# SensorBoard.net
KiCad netlist of a schematic drawn in EAGLE
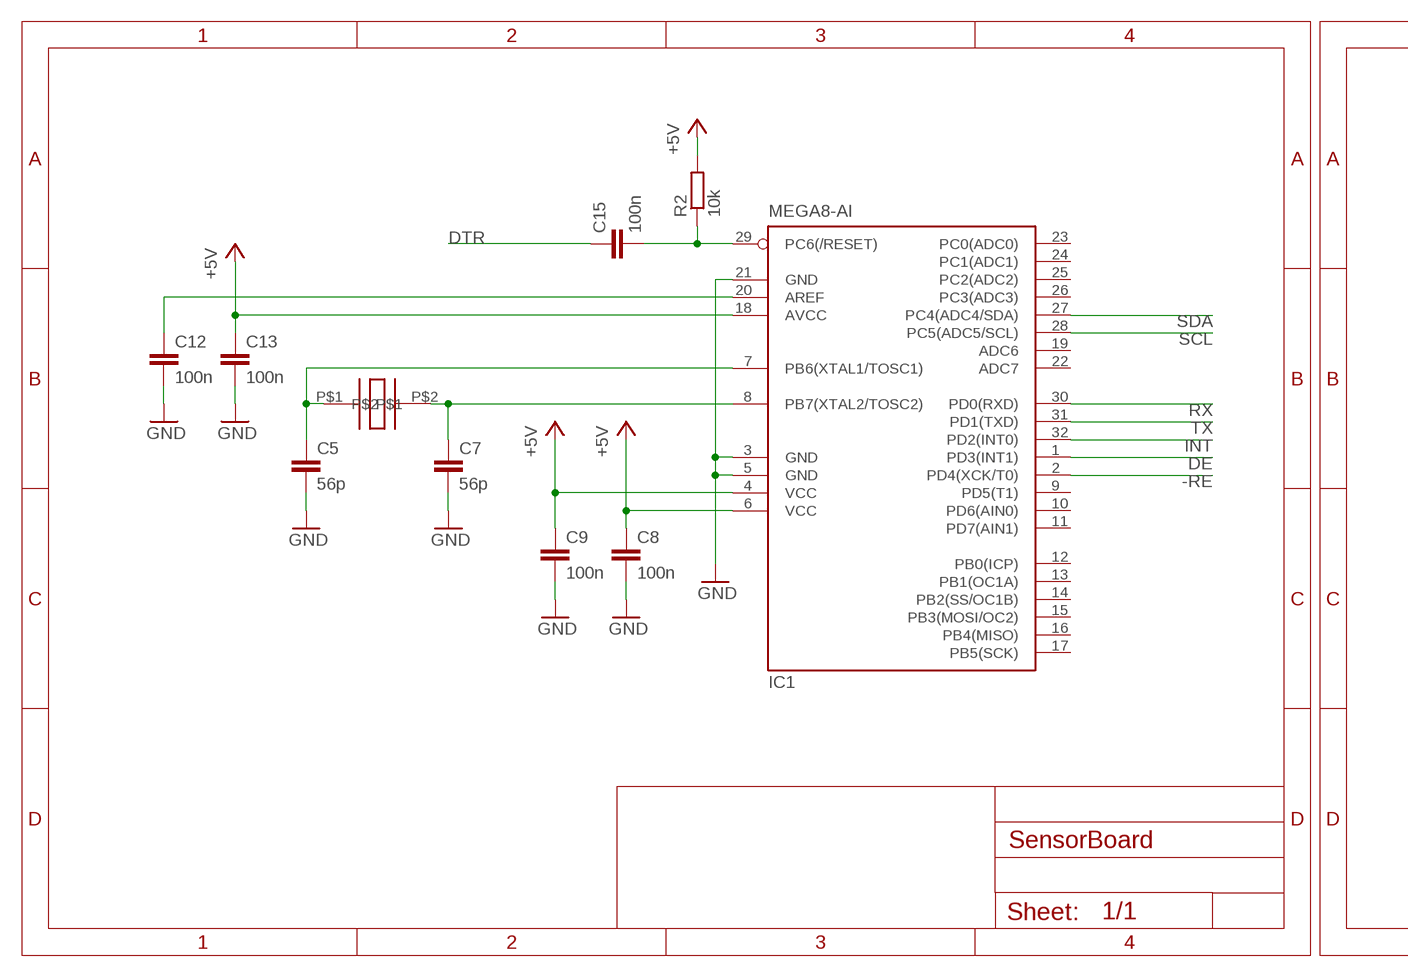
[diagram p0: schematic, sheet 1, part 1 of 2]
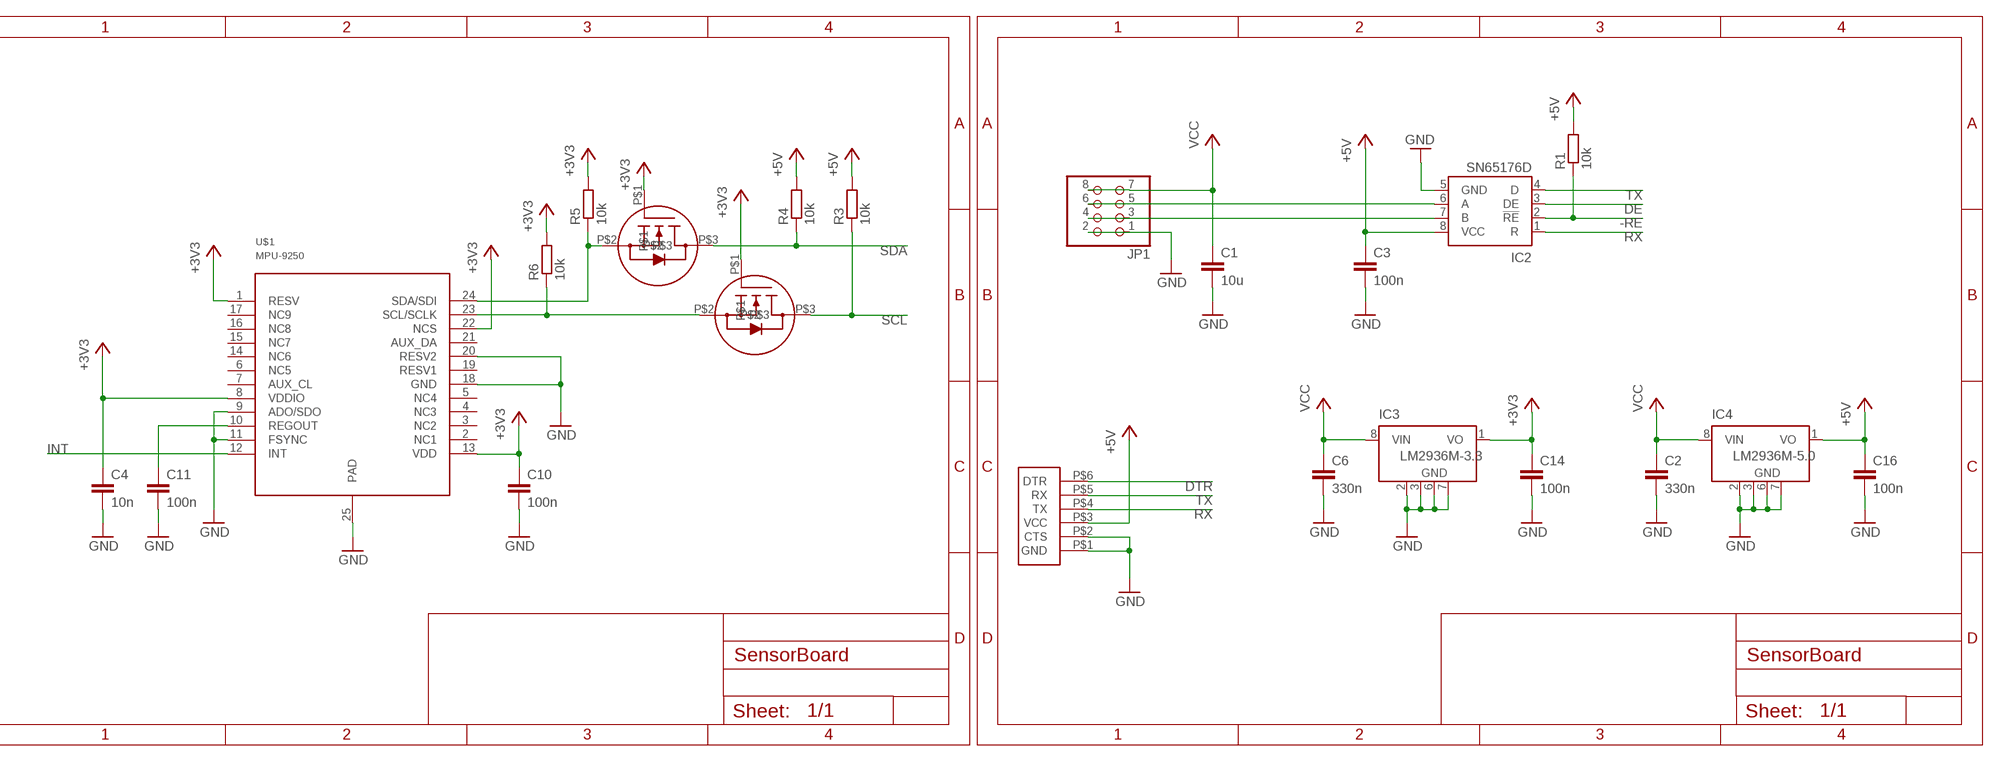
[diagram p1: schematic, sheet 1, part 2 of 2]

(export (version "E")
  (design (tool "Eeschema 10.0.6"))
  (components
    (comp (ref "C1")
      (value "10u")
      (footprint "eagle-import:C0805")
      (libsource (lib "eagle-import") (part "C-EUC0805"))
    )
    (comp (ref "C2")
      (value "330n")
      (footprint "eagle-import:C0603")
      (libsource (lib "eagle-import") (part "C-EUC0603"))
    )
    (comp (ref "C3")
      (value "100n")
      (footprint "eagle-import:C0603")
      (libsource (lib "eagle-import") (part "C-EUC0603"))
    )
    (comp (ref "C4")
      (value "10n")
      (footprint "eagle-import:C0603")
      (libsource (lib "eagle-import") (part "C-EUC0603"))
    )
    (comp (ref "C5")
      (value "56p")
      (footprint "eagle-import:C0603")
      (libsource (lib "eagle-import") (part "C-EUC0603"))
    )
    (comp (ref "C6")
      (value "330n")
      (footprint "eagle-import:C0603")
      (libsource (lib "eagle-import") (part "C-EUC0603"))
    )
    (comp (ref "C7")
      (value "56p")
      (footprint "eagle-import:C0603")
      (libsource (lib "eagle-import") (part "C-EUC0603"))
    )
    (comp (ref "C8")
      (value "100n")
      (footprint "eagle-import:C0603")
      (libsource (lib "eagle-import") (part "C-EUC0603"))
    )
    (comp (ref "C9")
      (value "100n")
      (footprint "eagle-import:C0603")
      (libsource (lib "eagle-import") (part "C-EUC0603"))
    )
    (comp (ref "C10")
      (value "100n")
      (footprint "eagle-import:C0603")
      (libsource (lib "eagle-import") (part "C-EUC0603"))
    )
    (comp (ref "C11")
      (value "100n")
      (footprint "eagle-import:C0603")
      (libsource (lib "eagle-import") (part "C-EUC0603"))
    )
    (comp (ref "C12")
      (value "100n")
      (footprint "eagle-import:C0603")
      (libsource (lib "eagle-import") (part "C-EUC0603"))
    )
    (comp (ref "C13")
      (value "100n")
      (footprint "eagle-import:C0603")
      (libsource (lib "eagle-import") (part "C-EUC0603"))
    )
    (comp (ref "C14")
      (value "100n")
      (footprint "eagle-import:C0603")
      (libsource (lib "eagle-import") (part "C-EUC0603"))
    )
    (comp (ref "C15")
      (value "100n")
      (footprint "eagle-import:C0603")
      (libsource (lib "eagle-import") (part "C-EUC0603"))
    )
    (comp (ref "C16")
      (value "100n")
      (footprint "eagle-import:C0603")
      (libsource (lib "eagle-import") (part "C-EUC0603"))
    )
    (comp (ref "IC1")
      (value "MEGA8-AI")
      (footprint "eagle-import:TQFP32-08")
      (fields (field (name "MPN") "ATMEGA8-16AU"))
      (libsource (lib "eagle-import") (part "MEGA8-AI"))
    )
    (comp (ref "IC2")
      (value "SN65176D")
      (footprint "eagle-import:SO-08")
      (fields (field (name "MF") "TEXAS INSTRUMENTS") (field (name "MPN") "SN65176BD"))
      (libsource (lib "eagle-import") (part "SN65176D"))
    )
    (comp (ref "IC3")
      (value "LM2936M-3.3")
      (footprint "eagle-import:SO08")
      (fields (field (name "MF") "NATIONAL SEMICONDUCTOR") (field (name "MPN") "LM2936M-3.3/NOPB"))
      (libsource (lib "eagle-import") (part "LM2936M?-3.3"))
    )
    (comp (ref "IC4")
      (value "LM2936M-5.0")
      (footprint "eagle-import:SO08")
      (fields (field (name "MF") "NATIONAL SEMICONDUCTOR") (field (name "MPN") "LM2936M-5.0/NOPB"))
      (libsource (lib "eagle-import") (part "LM2936M?-5.0"))
    )
    (comp (ref "JP1")
      (value "PINHD-2X4/90")
      (footprint "eagle-import:2X04_90")
      (libsource (lib "eagle-import") (part "PINHD-2X4/90"))
    )
    (comp (ref "R1")
      (value "10k")
      (footprint "eagle-import:R0603")
      (libsource (lib "eagle-import") (part "R-EU_R0603"))
    )
    (comp (ref "R2")
      (value "10k")
      (footprint "eagle-import:R0603")
      (libsource (lib "eagle-import") (part "R-EU_R0603"))
    )
    (comp (ref "R3")
      (value "10k")
      (footprint "eagle-import:R0603")
      (libsource (lib "eagle-import") (part "R-EU_R0603"))
    )
    (comp (ref "R4")
      (value "10k")
      (footprint "eagle-import:R0603")
      (libsource (lib "eagle-import") (part "R-EU_R0603"))
    )
    (comp (ref "R5")
      (value "10k")
      (footprint "eagle-import:R0603")
      (libsource (lib "eagle-import") (part "R-EU_R0603"))
    )
    (comp (ref "R6")
      (value "10k")
      (footprint "eagle-import:R0603")
      (libsource (lib "eagle-import") (part "R-EU_R0603"))
    )
    (comp (ref "U$1")
      (value "MPU-9250")
      (footprint "eagle-import:LEAD-QFN24")
      (libsource (lib "eagle-import") (part "MPU-9250"))
    )
    (comp (ref "U$2")
      (value "2N7002E")
      (footprint "eagle-import:SOT-23-3")
      (libsource (lib "eagle-import") (part "2N7002E"))
    )
    (comp (ref "U$3")
      (value "2N7002E")
      (footprint "eagle-import:SOT-23-3")
      (libsource (lib "eagle-import") (part "2N7002E"))
    )
    (comp (ref "U$4")
      (value "LFXTAL003240BULK")
      (footprint "eagle-import:LFXTAL003240BULK")
      (libsource (lib "eagle-import") (part "LFXTAL003240BULK"))
    )
    (comp (ref "U$5")
      (value "FTDI-PINHEADER")
      (footprint "eagle-import:FTDI-PINHEADER")
      (libsource (lib "eagle-import") (part "FTDI-PINHEADER"))
    )
  )
  (nets
    (net (code "1") (name "+3V3") (class "Default")
      (node (ref "C10") (pin "1") (pinfunction "1_1") (pintype "passive"))
      (node (ref "C14") (pin "1") (pinfunction "1_1") (pintype "passive"))
      (node (ref "C4") (pin "1") (pinfunction "1_1") (pintype "passive"))
      (node (ref "IC3") (pin "1") (pinfunction "VO_1") (pintype "passive"))
      (node (ref "R5") (pin "2") (pinfunction "2_2") (pintype "passive"))
      (node (ref "R6") (pin "2") (pinfunction "2_2") (pintype "passive"))
      (node (ref "U$1") (pin "1") (pinfunction "RESV_1") (pintype "bidirectional"))
      (node (ref "U$1") (pin "13") (pinfunction "VDD_13") (pintype "bidirectional"))
      (node (ref "U$1") (pin "22") (pinfunction "NCS_22") (pintype "bidirectional"))
      (node (ref "U$1") (pin "8") (pinfunction "VDDIO_8") (pintype "bidirectional"))
      (node (ref "U$2") (pin "P$1") (pinfunction "P$1_P$1") (pintype "bidirectional"))
      (node (ref "U$3") (pin "P$1") (pinfunction "P$1_P$1") (pintype "bidirectional"))
    )
    (net (code "2") (name "+5V") (class "Default")
      (node (ref "C13") (pin "1") (pinfunction "1_1") (pintype "passive"))
      (node (ref "C16") (pin "1") (pinfunction "1_1") (pintype "passive"))
      (node (ref "C3") (pin "1") (pinfunction "1_1") (pintype "passive"))
      (node (ref "C8") (pin "1") (pinfunction "1_1") (pintype "passive"))
      (node (ref "C9") (pin "1") (pinfunction "1_1") (pintype "passive"))
      (node (ref "IC1") (pin "18") (pinfunction "AVCC_18") (pintype "power_in"))
      (node (ref "IC1") (pin "4") (pinfunction "VCC_4") (pintype "power_in"))
      (node (ref "IC1") (pin "6") (pinfunction "VCC_6") (pintype "power_in"))
      (node (ref "IC2") (pin "8") (pinfunction "VCC_8") (pintype "input"))
      (node (ref "IC4") (pin "1") (pinfunction "VO_1") (pintype "passive"))
      (node (ref "R1") (pin "2") (pinfunction "2_2") (pintype "passive"))
      (node (ref "R2") (pin "2") (pinfunction "2_2") (pintype "passive"))
      (node (ref "R3") (pin "2") (pinfunction "2_2") (pintype "passive"))
      (node (ref "R4") (pin "2") (pinfunction "2_2") (pintype "passive"))
      (node (ref "U$5") (pin "P$3") (pinfunction "VCC_P$3") (pintype "bidirectional"))
    )
    (net (code "3") (name "/-RE") (class "Default")
      (node (ref "IC1") (pin "2") (pinfunction "PD4(XCK/T0)_2") (pintype "bidirectional"))
      (node (ref "IC2") (pin "2") (pinfunction "~{RE}_2") (pintype "input"))
      (node (ref "R1") (pin "1") (pinfunction "1_1") (pintype "passive"))
    )
    (net (code "4") (name "/DE") (class "Default")
      (node (ref "IC1") (pin "1") (pinfunction "PD3(INT1)_1") (pintype "bidirectional"))
      (node (ref "IC2") (pin "3") (pinfunction "DE_3") (pintype "input"))
    )
    (net (code "5") (name "/DTR") (class "Default")
      (node (ref "C15") (pin "1") (pinfunction "1_1") (pintype "passive"))
      (node (ref "U$5") (pin "P$6") (pinfunction "DTR_P$6") (pintype "bidirectional"))
    )
    (net (code "6") (name "/INT") (class "Default")
      (node (ref "IC1") (pin "32") (pinfunction "PD2(INT0)_32") (pintype "bidirectional"))
      (node (ref "U$1") (pin "12") (pinfunction "INT_12") (pintype "bidirectional"))
    )
    (net (code "7") (name "/RX") (class "Default")
      (node (ref "IC1") (pin "30") (pinfunction "PD0(RXD)_30") (pintype "bidirectional"))
      (node (ref "IC2") (pin "1") (pinfunction "R_1") (pintype "input"))
      (node (ref "U$5") (pin "P$4") (pinfunction "TX_P$4") (pintype "bidirectional"))
    )
    (net (code "8") (name "/SCL") (class "Default")
      (node (ref "IC1") (pin "28") (pinfunction "PC5(ADC5/SCL)_28") (pintype "bidirectional"))
      (node (ref "R3") (pin "1") (pinfunction "1_1") (pintype "passive"))
      (node (ref "U$2") (pin "P$3") (pinfunction "P$3_P$3") (pintype "bidirectional"))
    )
    (net (code "9") (name "/SDA") (class "Default")
      (node (ref "IC1") (pin "27") (pinfunction "PC4(ADC4/SDA)_27") (pintype "bidirectional"))
      (node (ref "R4") (pin "1") (pinfunction "1_1") (pintype "passive"))
      (node (ref "U$3") (pin "P$3") (pinfunction "P$3_P$3") (pintype "bidirectional"))
    )
    (net (code "10") (name "/TX") (class "Default")
      (node (ref "IC1") (pin "31") (pinfunction "PD1(TXD)_31") (pintype "bidirectional"))
      (node (ref "IC2") (pin "4") (pinfunction "D_4") (pintype "input"))
      (node (ref "U$5") (pin "P$5") (pinfunction "RX_P$5") (pintype "bidirectional"))
    )
    (net (code "11") (name "GND") (class "Default")
      (node (ref "C1") (pin "2") (pinfunction "2_2") (pintype "passive"))
      (node (ref "C10") (pin "2") (pinfunction "2_2") (pintype "passive"))
      (node (ref "C11") (pin "2") (pinfunction "2_2") (pintype "passive"))
      (node (ref "C12") (pin "2") (pinfunction "2_2") (pintype "passive"))
      (node (ref "C13") (pin "2") (pinfunction "2_2") (pintype "passive"))
      (node (ref "C14") (pin "2") (pinfunction "2_2") (pintype "passive"))
      (node (ref "C16") (pin "2") (pinfunction "2_2") (pintype "passive"))
      (node (ref "C2") (pin "2") (pinfunction "2_2") (pintype "passive"))
      (node (ref "C3") (pin "2") (pinfunction "2_2") (pintype "passive"))
      (node (ref "C4") (pin "2") (pinfunction "2_2") (pintype "passive"))
      (node (ref "C5") (pin "2") (pinfunction "2_2") (pintype "passive"))
      (node (ref "C6") (pin "2") (pinfunction "2_2") (pintype "passive"))
      (node (ref "C7") (pin "2") (pinfunction "2_2") (pintype "passive"))
      (node (ref "C8") (pin "2") (pinfunction "2_2") (pintype "passive"))
      (node (ref "C9") (pin "2") (pinfunction "2_2") (pintype "passive"))
      (node (ref "IC1") (pin "21") (pinfunction "GND_21") (pintype "power_in"))
      (node (ref "IC1") (pin "3") (pinfunction "GND_3") (pintype "power_in"))
      (node (ref "IC1") (pin "5") (pinfunction "GND_5") (pintype "power_in"))
      (node (ref "IC2") (pin "5") (pinfunction "GND_5") (pintype "input"))
      (node (ref "IC3") (pin "2") (pinfunction "GND_2") (pintype "passive"))
      (node (ref "IC3") (pin "3") (pinfunction "GND_3") (pintype "passive"))
      (node (ref "IC3") (pin "6") (pinfunction "GND_6") (pintype "passive"))
      (node (ref "IC3") (pin "7") (pinfunction "GND_7") (pintype "passive"))
      (node (ref "IC4") (pin "2") (pinfunction "GND_2") (pintype "passive"))
      (node (ref "IC4") (pin "3") (pinfunction "GND_3") (pintype "passive"))
      (node (ref "IC4") (pin "6") (pinfunction "GND_6") (pintype "passive"))
      (node (ref "IC4") (pin "7") (pinfunction "GND_7") (pintype "passive"))
      (node (ref "JP1") (pin "1") (pinfunction "1_1") (pintype "passive"))
      (node (ref "JP1") (pin "2") (pinfunction "2_2") (pintype "passive"))
      (node (ref "U$1") (pin "11") (pinfunction "FSYNC_11") (pintype "bidirectional"))
      (node (ref "U$1") (pin "18") (pinfunction "GND_18") (pintype "bidirectional"))
      (node (ref "U$1") (pin "20") (pinfunction "RESV2_20") (pintype "bidirectional"))
      (node (ref "U$1") (pin "25") (pinfunction "PAD_25") (pintype "bidirectional"))
      (node (ref "U$1") (pin "9") (pinfunction "ADO/SDO_9") (pintype "bidirectional"))
      (node (ref "U$5") (pin "P$1") (pinfunction "GND_P$1") (pintype "bidirectional"))
      (node (ref "U$5") (pin "P$2") (pinfunction "CTS_P$2") (pintype "bidirectional"))
    )
    (net (code "12") (name "Net-(IC1-AREF)") (class "Default")
      (node (ref "C12") (pin "1") (pinfunction "1_1") (pintype "passive"))
      (node (ref "IC1") (pin "20") (pinfunction "AREF_20") (pintype "passive"))
    )
    (net (code "13") (name "Net-(IC1-PB6(XTAL1{slash}TOSC1))") (class "Default")
      (node (ref "C5") (pin "1") (pinfunction "1_1") (pintype "passive"))
      (node (ref "IC1") (pin "7") (pinfunction "PB6(XTAL1/TOSC1)_7") (pintype "bidirectional"))
      (node (ref "U$4") (pin "P$1") (pinfunction "P$1_P$1") (pintype "bidirectional"))
    )
    (net (code "14") (name "Net-(IC1-PB7(XTAL2{slash}TOSC2))") (class "Default")
      (node (ref "C7") (pin "1") (pinfunction "1_1") (pintype "passive"))
      (node (ref "IC1") (pin "8") (pinfunction "PB7(XTAL2/TOSC2)_8") (pintype "bidirectional"))
      (node (ref "U$4") (pin "P$2") (pinfunction "P$2_P$2") (pintype "bidirectional"))
    )
    (net (code "15") (name "Net-(IC1-PC6({slash}RESET))") (class "Default")
      (node (ref "C15") (pin "2") (pinfunction "2_2") (pintype "passive"))
      (node (ref "IC1") (pin "29") (pinfunction "PC6(/RESET)_29") (pintype "bidirectional"))
      (node (ref "R2") (pin "1") (pinfunction "1_1") (pintype "passive"))
    )
    (net (code "16") (name "Net-(IC2-A)") (class "Default")
      (node (ref "IC2") (pin "6") (pinfunction "A_6") (pintype "input"))
      (node (ref "JP1") (pin "5") (pinfunction "5_5") (pintype "passive"))
      (node (ref "JP1") (pin "6") (pinfunction "6_6") (pintype "passive"))
    )
    (net (code "17") (name "Net-(IC2-B)") (class "Default")
      (node (ref "IC2") (pin "7") (pinfunction "B_7") (pintype "input"))
      (node (ref "JP1") (pin "3") (pinfunction "3_3") (pintype "passive"))
      (node (ref "JP1") (pin "4") (pinfunction "4_4") (pintype "passive"))
    )
    (net (code "18") (name "Net-(U$1-REGOUT)") (class "Default")
      (node (ref "C11") (pin "1") (pinfunction "1_1") (pintype "passive"))
      (node (ref "U$1") (pin "10") (pinfunction "REGOUT_10") (pintype "bidirectional"))
    )
    (net (code "19") (name "Net-(U$1-SCL{slash}SCLK)") (class "Default")
      (node (ref "R6") (pin "1") (pinfunction "1_1") (pintype "passive"))
      (node (ref "U$1") (pin "23") (pinfunction "SCL/SCLK_23") (pintype "bidirectional"))
      (node (ref "U$2") (pin "P$2") (pinfunction "P$2_P$2") (pintype "bidirectional"))
    )
    (net (code "20") (name "Net-(U$1-SDA{slash}SDI)") (class "Default")
      (node (ref "R5") (pin "1") (pinfunction "1_1") (pintype "passive"))
      (node (ref "U$1") (pin "24") (pinfunction "SDA/SDI_24") (pintype "bidirectional"))
      (node (ref "U$3") (pin "P$2") (pinfunction "P$2_P$2") (pintype "bidirectional"))
    )
    (net (code "21") (name "VCC") (class "Default")
      (node (ref "C1") (pin "1") (pinfunction "1_1") (pintype "passive"))
      (node (ref "C2") (pin "1") (pinfunction "1_1") (pintype "passive"))
      (node (ref "C6") (pin "1") (pinfunction "1_1") (pintype "passive"))
      (node (ref "IC3") (pin "8") (pinfunction "VIN_8") (pintype "input"))
      (node (ref "IC4") (pin "8") (pinfunction "VIN_8") (pintype "input"))
      (node (ref "JP1") (pin "7") (pinfunction "7_7") (pintype "passive"))
      (node (ref "JP1") (pin "8") (pinfunction "8_8") (pintype "passive"))
    )
    (net (code "22") (name "unconnected-(IC1-ADC6-Pad19)") (class "Default")
      (node (ref "IC1") (pin "19") (pinfunction "ADC6_19") (pintype "bidirectional"))
    )
    (net (code "23") (name "unconnected-(IC1-ADC7-Pad22)") (class "Default")
      (node (ref "IC1") (pin "22") (pinfunction "ADC7_22") (pintype "bidirectional"))
    )
    (net (code "24") (name "unconnected-(IC1-PB0(ICP)-Pad12)") (class "Default")
      (node (ref "IC1") (pin "12") (pinfunction "PB0(ICP)_12") (pintype "bidirectional"))
    )
    (net (code "25") (name "unconnected-(IC1-PB1(OC1A)-Pad13)") (class "Default")
      (node (ref "IC1") (pin "13") (pinfunction "PB1(OC1A)_13") (pintype "bidirectional"))
    )
    (net (code "26") (name "unconnected-(IC1-PB2(SS{slash}OC1B)-Pad14)") (class "Default")
      (node (ref "IC1") (pin "14") (pinfunction "PB2(SS/OC1B)_14") (pintype "bidirectional"))
    )
    (net (code "27") (name "unconnected-(IC1-PB3(MOSI{slash}OC2)-Pad15)") (class "Default")
      (node (ref "IC1") (pin "15") (pinfunction "PB3(MOSI/OC2)_15") (pintype "bidirectional"))
    )
    (net (code "28") (name "unconnected-(IC1-PB4(MISO)-Pad16)") (class "Default")
      (node (ref "IC1") (pin "16") (pinfunction "PB4(MISO)_16") (pintype "bidirectional"))
    )
    (net (code "29") (name "unconnected-(IC1-PB5(SCK)-Pad17)") (class "Default")
      (node (ref "IC1") (pin "17") (pinfunction "PB5(SCK)_17") (pintype "bidirectional"))
    )
    (net (code "30") (name "unconnected-(IC1-PC0(ADC0)-Pad23)") (class "Default")
      (node (ref "IC1") (pin "23") (pinfunction "PC0(ADC0)_23") (pintype "bidirectional"))
    )
    (net (code "31") (name "unconnected-(IC1-PC1(ADC1)-Pad24)") (class "Default")
      (node (ref "IC1") (pin "24") (pinfunction "PC1(ADC1)_24") (pintype "bidirectional"))
    )
    (net (code "32") (name "unconnected-(IC1-PC2(ADC2)-Pad25)") (class "Default")
      (node (ref "IC1") (pin "25") (pinfunction "PC2(ADC2)_25") (pintype "bidirectional"))
    )
    (net (code "33") (name "unconnected-(IC1-PC3(ADC3)-Pad26)") (class "Default")
      (node (ref "IC1") (pin "26") (pinfunction "PC3(ADC3)_26") (pintype "bidirectional"))
    )
    (net (code "34") (name "unconnected-(IC1-PD5(T1)-Pad9)") (class "Default")
      (node (ref "IC1") (pin "9") (pinfunction "PD5(T1)_9") (pintype "bidirectional"))
    )
    (net (code "35") (name "unconnected-(IC1-PD6(AIN0)-Pad10)") (class "Default")
      (node (ref "IC1") (pin "10") (pinfunction "PD6(AIN0)_10") (pintype "bidirectional"))
    )
    (net (code "36") (name "unconnected-(IC1-PD7(AIN1)-Pad11)") (class "Default")
      (node (ref "IC1") (pin "11") (pinfunction "PD7(AIN1)_11") (pintype "bidirectional"))
    )
    (net (code "37") (name "unconnected-(U$1-AUX_CL-Pad7)") (class "Default")
      (node (ref "U$1") (pin "7") (pinfunction "AUX_CL_7") (pintype "bidirectional"))
    )
    (net (code "38") (name "unconnected-(U$1-AUX_DA-Pad21)") (class "Default")
      (node (ref "U$1") (pin "21") (pinfunction "AUX_DA_21") (pintype "bidirectional"))
    )
    (net (code "39") (name "unconnected-(U$1-NC1-Pad2)") (class "Default")
      (node (ref "U$1") (pin "2") (pinfunction "NC1_2") (pintype "bidirectional"))
    )
    (net (code "40") (name "unconnected-(U$1-NC2-Pad3)") (class "Default")
      (node (ref "U$1") (pin "3") (pinfunction "NC2_3") (pintype "bidirectional"))
    )
    (net (code "41") (name "unconnected-(U$1-NC3-Pad4)") (class "Default")
      (node (ref "U$1") (pin "4") (pinfunction "NC3_4") (pintype "bidirectional"))
    )
    (net (code "42") (name "unconnected-(U$1-NC4-Pad5)") (class "Default")
      (node (ref "U$1") (pin "5") (pinfunction "NC4_5") (pintype "bidirectional"))
    )
    (net (code "43") (name "unconnected-(U$1-NC5-Pad6)") (class "Default")
      (node (ref "U$1") (pin "6") (pinfunction "NC5_6") (pintype "bidirectional"))
    )
    (net (code "44") (name "unconnected-(U$1-NC6-Pad14)") (class "Default")
      (node (ref "U$1") (pin "14") (pinfunction "NC6_14") (pintype "bidirectional"))
    )
    (net (code "45") (name "unconnected-(U$1-NC7-Pad15)") (class "Default")
      (node (ref "U$1") (pin "15") (pinfunction "NC7_15") (pintype "bidirectional"))
    )
    (net (code "46") (name "unconnected-(U$1-NC8-Pad16)") (class "Default")
      (node (ref "U$1") (pin "16") (pinfunction "NC8_16") (pintype "bidirectional"))
    )
    (net (code "47") (name "unconnected-(U$1-NC9-Pad17)") (class "Default")
      (node (ref "U$1") (pin "17") (pinfunction "NC9_17") (pintype "bidirectional"))
    )
    (net (code "48") (name "unconnected-(U$1-RESV1-Pad19)") (class "Default")
      (node (ref "U$1") (pin "19") (pinfunction "RESV1_19") (pintype "bidirectional"))
    )
  )
)
